# norbi_lm_interface.net
KiCad netlist of a schematic drawn in Altium Designer
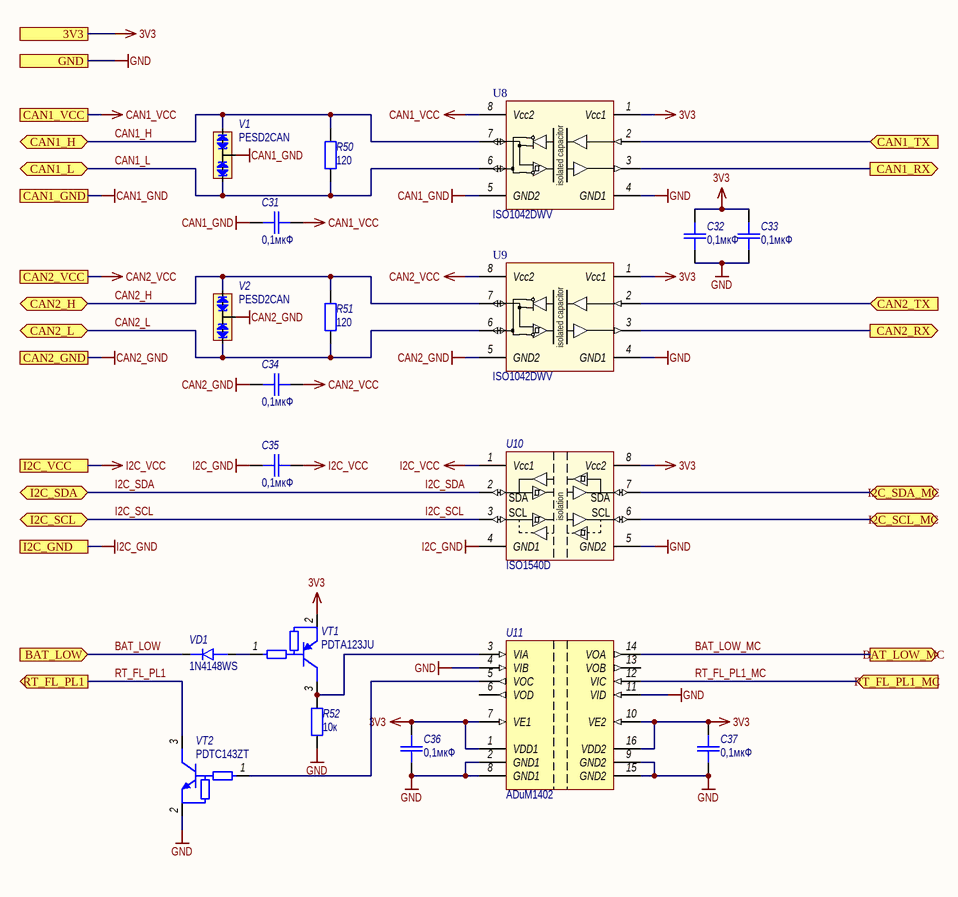
[diagram p0: norbi_lm_interface.SchDoc]

(export (version "E")
  (design (tool "Eeschema 10.0.6"))
  (components
    (comp (ref "C31")
      (value "0,1мкФ")
      (footprint "CR-0603")
      (description "Конденсатор для поверхностного монтажа")
      (libsource (lib "my_passive") (part "C_smd"))
    )
    (comp (ref "C32")
      (value "0,1мкФ")
      (footprint "CR-0603")
      (description "Конденсатор для поверхностного монтажа")
      (libsource (lib "my_passive") (part "C_smd"))
    )
    (comp (ref "C33")
      (value "0,1мкФ")
      (footprint "CR-0603")
      (description "Конденсатор для поверхностного монтажа")
      (libsource (lib "my_passive") (part "C_smd"))
    )
    (comp (ref "C34")
      (value "0,1мкФ")
      (footprint "CR-0603")
      (description "Конденсатор для поверхностного монтажа")
      (libsource (lib "my_passive") (part "C_smd"))
    )
    (comp (ref "C35")
      (value "0,1мкФ")
      (footprint "CR-0603")
      (description "Конденсатор для поверхностного монтажа")
      (libsource (lib "my_passive") (part "C_smd"))
    )
    (comp (ref "C36")
      (value "0,1мкФ")
      (footprint "CR-0603")
      (description "Конденсатор для поверхностного монтажа")
      (libsource (lib "my_passive") (part "C_smd"))
    )
    (comp (ref "C37")
      (value "0,1мкФ")
      (footprint "CR-0603")
      (description "Конденсатор для поверхностного монтажа")
      (libsource (lib "my_passive") (part "C_smd"))
    )
    (comp (ref "R50")
      (value "120")
      (footprint "CR-0603")
      (description "Резистор для поверхностного монтажа")
      (libsource (lib "") (part "R_smd_1"))
    )
    (comp (ref "R51")
      (value "120")
      (footprint "CR-0603")
      (description "Резистор для поверхностного монтажа")
      (libsource (lib "") (part "R_smd_1"))
    )
    (comp (ref "R52")
      (value "10к")
      (footprint "CR-0603")
      (description "Резистор для поверхностного монтажа")
      (libsource (lib "my_passive") (part "R_smd"))
    )
    (comp (ref "U8")
      (value "ISO1042")
      (footprint "SOIC-8-WIDE")
      (description "Isolated CAN Transceiver")
      (fields (field (name "НАИМЕНОВАНИЕ") "ISO1042DWV"))
      (libsource (lib "my_integrated_circuit") (part "ISO1042"))
    )
    (comp (ref "U9")
      (value "ISO1042")
      (footprint "SOIC-8-WIDE")
      (description "Isolated CAN Transceiver")
      (fields (field (name "НАИМЕНОВАНИЕ") "ISO1042DWV"))
      (libsource (lib "my_integrated_circuit") (part "ISO1042"))
    )
    (comp (ref "U10")
      (value "ISO1540")
      (footprint "SOIC-8")
      (description "Low-Power Bidirectional I2C Isolators")
      (fields (field (name "НАИМЕНОВАНИЕ") "ISO1540D"))
      (libsource (lib "my_integrated_circuit") (part "ISO154x"))
    )
    (comp (ref "U11")
      (value "ADuM1402")
      (footprint "SOIC-16-WIDE")
      (description "Quad Channel Digital Isolator, 2.5 KV rms Insulation Rating")
      (fields (field (name "НАИМЕНОВАНИЕ") "ADuM1402"))
      (libsource (lib "my_integrated_circuit") (part "ADuM1402"))
    )
    (comp (ref "V1")
      (value "PESD2CAN")
      (footprint "SOT-23")
      (description "CAN bus ESD protection diode")
      (fields (field (name "НАИМЕНОВАНИЕ") "PESD2CAN"))
      (libsource (lib "my_semicond") (part "PESD2CAN"))
    )
    (comp (ref "V2")
      (value "PESD2CAN")
      (footprint "SOT-23")
      (description "CAN bus ESD protection diode")
      (fields (field (name "НАИМЕНОВАНИЕ") "PESD2CAN"))
      (libsource (lib "my_semicond") (part "PESD2CAN"))
    )
    (comp (ref "VD1")
      (value "1N4148WS")
      (footprint "SOD-323")
      (description "Diod 150 mA 100V")
      (libsource (lib "my_semicond") (part "BAT60A"))
    )
    (comp (ref "VT1")
      (value "PDTA123JU")
      (footprint "SOT-323 (SC-70)")
      (description "Digital Transistor (resistor-equipped transistors), R1=R2=2k, PNP Transistor, 3-Pin SC-70")
      (fields (field (name "НАИМЕНОВАНИЕ") "PDTA123JU"))
      (libsource (lib "my_semicond") (part "PDTA123JU"))
    )
    (comp (ref "VT2")
      (value "PDTC143ZT")
      (footprint "SOT-23")
      (description "Digital Transistor (BRT), R1=4.7 kOhm, R2=47 kOhm, NPN Transistor, 3-Pin")
      (fields (field (name "НАИМЕНОВАНИЕ") "PDTC143ZT"))
      (libsource (lib "my_semicond") (part "PDTC143ZT"))
    )
  )
  (nets
    (net (code "1") (name "/BAT_LOW") (class "Default")
      (node (ref "VD1") (pin "1") (pinfunction "Cathode_1") (pintype "passive"))
    )
    (net (code "2") (name "/BAT_LOW_MC") (class "Default")
      (node (ref "U11") (pin "14") (pinfunction "VOA_14") (pintype "output"))
    )
    (net (code "3") (name "/CAN1_H") (class "Default")
      (node (ref "R50") (pin "2") (pinfunction "2_2") (pintype "passive"))
      (node (ref "U8") (pin "7") (pinfunction "CANH_7") (pintype "bidirectional"))
      (node (ref "V1") (pin "1") (pinfunction "C1_1") (pintype "passive"))
    )
    (net (code "4") (name "/CAN1_L") (class "Default")
      (node (ref "R50") (pin "1") (pinfunction "1_1") (pintype "passive"))
      (node (ref "U8") (pin "6") (pinfunction "CANL_6") (pintype "bidirectional"))
      (node (ref "V1") (pin "2") (pinfunction "C2_2") (pintype "passive"))
    )
    (net (code "5") (name "/CAN1_RX") (class "Default")
      (node (ref "U8") (pin "3") (pinfunction "RXD_3") (pintype "output"))
    )
    (net (code "6") (name "/CAN1_TX") (class "Default")
      (node (ref "U8") (pin "2") (pinfunction "TXD_2") (pintype "input"))
    )
    (net (code "7") (name "/CAN2_H") (class "Default")
      (node (ref "R51") (pin "2") (pinfunction "2_2") (pintype "passive"))
      (node (ref "U9") (pin "7") (pinfunction "CANH_7") (pintype "bidirectional"))
      (node (ref "V2") (pin "1") (pinfunction "C1_1") (pintype "passive"))
    )
    (net (code "8") (name "/CAN2_L") (class "Default")
      (node (ref "R51") (pin "1") (pinfunction "1_1") (pintype "passive"))
      (node (ref "U9") (pin "6") (pinfunction "CANL_6") (pintype "bidirectional"))
      (node (ref "V2") (pin "2") (pinfunction "C2_2") (pintype "passive"))
    )
    (net (code "9") (name "/CAN2_RX") (class "Default")
      (node (ref "U9") (pin "3") (pinfunction "RXD_3") (pintype "output"))
    )
    (net (code "10") (name "/CAN2_TX") (class "Default")
      (node (ref "U9") (pin "2") (pinfunction "TXD_2") (pintype "input"))
    )
    (net (code "11") (name "/I2C_SCL") (class "Default")
      (node (ref "U10") (pin "3") (pinfunction "SCL_3") (pintype "bidirectional"))
    )
    (net (code "12") (name "/I2C_SCL_MC") (class "Default")
      (node (ref "U10") (pin "6") (pinfunction "SCL_6") (pintype "bidirectional"))
    )
    (net (code "13") (name "/I2C_SDA") (class "Default")
      (node (ref "U10") (pin "2") (pinfunction "SDA_2") (pintype "bidirectional"))
    )
    (net (code "14") (name "/I2C_SDA_MC") (class "Default")
      (node (ref "U10") (pin "7") (pinfunction "SDA_7") (pintype "bidirectional"))
    )
    (net (code "15") (name "/RT_FL_PL1") (class "Default")
      (node (ref "VT2") (pin "3") (pinfunction "C_3") (pintype "passive"))
    )
    (net (code "16") (name "/RT_FL_PL1_MC") (class "Default")
      (node (ref "U11") (pin "12") (pinfunction "VIC_12") (pintype "input"))
    )
    (net (code "17") (name "3V3") (class "Default")
      (node (ref "C32") (pin "2") (pinfunction "2_2") (pintype "passive"))
      (node (ref "C33") (pin "2") (pinfunction "2_2") (pintype "passive"))
      (node (ref "C36") (pin "2") (pinfunction "2_2") (pintype "passive"))
      (node (ref "C37") (pin "2") (pinfunction "2_2") (pintype "passive"))
      (node (ref "U10") (pin "8") (pinfunction "Vcc2_8") (pintype "power_in"))
      (node (ref "U11") (pin "1") (pinfunction "VDD1_1") (pintype "power_in"))
      (node (ref "U11") (pin "10") (pinfunction "VE2_10") (pintype "input"))
      (node (ref "U11") (pin "16") (pinfunction "VDD2_16") (pintype "power_in"))
      (node (ref "U11") (pin "7") (pinfunction "VE1_7") (pintype "input"))
      (node (ref "U8") (pin "1") (pinfunction "Vcc1_1") (pintype "power_in"))
      (node (ref "U9") (pin "1") (pinfunction "Vcc1_1") (pintype "power_in"))
      (node (ref "VT1") (pin "2") (pinfunction "E_2") (pintype "passive"))
    )
    (net (code "18") (name "CAN1_GND") (class "Default")
      (node (ref "C31") (pin "1") (pinfunction "1_1") (pintype "passive"))
      (node (ref "U8") (pin "5") (pinfunction "GND2_5") (pintype "power_in"))
      (node (ref "V1") (pin "3") (pinfunction "CC_3") (pintype "passive"))
    )
    (net (code "19") (name "CAN1_VCC") (class "Default")
      (node (ref "C31") (pin "2") (pinfunction "2_2") (pintype "passive"))
      (node (ref "U8") (pin "8") (pinfunction "Vcc2_8") (pintype "power_in"))
    )
    (net (code "20") (name "CAN2_GND") (class "Default")
      (node (ref "C34") (pin "1") (pinfunction "1_1") (pintype "passive"))
      (node (ref "U9") (pin "5") (pinfunction "GND2_5") (pintype "power_in"))
      (node (ref "V2") (pin "3") (pinfunction "CC_3") (pintype "passive"))
    )
    (net (code "21") (name "CAN2_VCC") (class "Default")
      (node (ref "C34") (pin "2") (pinfunction "2_2") (pintype "passive"))
      (node (ref "U9") (pin "8") (pinfunction "Vcc2_8") (pintype "power_in"))
    )
    (net (code "22") (name "GND") (class "Default")
      (node (ref "C32") (pin "1") (pinfunction "1_1") (pintype "passive"))
      (node (ref "C33") (pin "1") (pinfunction "1_1") (pintype "passive"))
      (node (ref "C36") (pin "1") (pinfunction "1_1") (pintype "passive"))
      (node (ref "C37") (pin "1") (pinfunction "1_1") (pintype "passive"))
      (node (ref "R52") (pin "2") (pinfunction "2_2") (pintype "passive"))
      (node (ref "U10") (pin "5") (pinfunction "GND2_5") (pintype "power_in"))
      (node (ref "U11") (pin "11") (pinfunction "VID_11") (pintype "input"))
      (node (ref "U11") (pin "15") (pinfunction "GND2_15") (pintype "power_in"))
      (node (ref "U11") (pin "2") (pinfunction "GND1_2") (pintype "power_in"))
      (node (ref "U11") (pin "4") (pinfunction "VIB_4") (pintype "input"))
      (node (ref "U11") (pin "8") (pinfunction "GND1_8") (pintype "power_in"))
      (node (ref "U11") (pin "9") (pinfunction "GND2_9") (pintype "power_in"))
      (node (ref "U8") (pin "4") (pinfunction "GND1_4") (pintype "power_in"))
      (node (ref "U9") (pin "4") (pinfunction "GND1_4") (pintype "power_in"))
      (node (ref "VT2") (pin "2") (pinfunction "E_2") (pintype "passive"))
    )
    (net (code "23") (name "I2C_GND") (class "Default")
      (node (ref "C35") (pin "1") (pinfunction "1_1") (pintype "passive"))
      (node (ref "U10") (pin "4") (pinfunction "GND1_4") (pintype "power_in"))
    )
    (net (code "24") (name "I2C_VCC") (class "Default")
      (node (ref "C35") (pin "2") (pinfunction "2_2") (pintype "passive"))
      (node (ref "U10") (pin "1") (pinfunction "Vcc1_1") (pintype "power_in"))
    )
    (net (code "25") (name "Net-(U11-VIA)") (class "Default")
      (node (ref "R52") (pin "1") (pinfunction "1_1") (pintype "passive"))
      (node (ref "U11") (pin "3") (pinfunction "VIA_3") (pintype "input"))
      (node (ref "VT1") (pin "3") (pinfunction "C_3") (pintype "passive"))
    )
    (net (code "26") (name "Net-(U11-VOC)") (class "Default")
      (node (ref "U11") (pin "5") (pinfunction "VOC_5") (pintype "output"))
      (node (ref "VT2") (pin "1") (pinfunction "B_1") (pintype "passive"))
    )
    (net (code "27") (name "Net-(VD1-Anode)") (class "Default")
      (node (ref "VD1") (pin "2") (pinfunction "Anode_2") (pintype "passive"))
      (node (ref "VT1") (pin "1") (pinfunction "B_1") (pintype "passive"))
    )
    (net (code "28") (name "unconnected-(U11-VOB-Pad13)") (class "Default")
      (node (ref "U11") (pin "13") (pinfunction "VOB_13") (pintype "output"))
    )
    (net (code "29") (name "unconnected-(U11-VOD-Pad6)") (class "Default")
      (node (ref "U11") (pin "6") (pinfunction "VOD_6") (pintype "output"))
    )
  )
)
